# Xonik_Noise_A6_w_logo.net
KiCad netlist of a schematic drawn in EAGLE
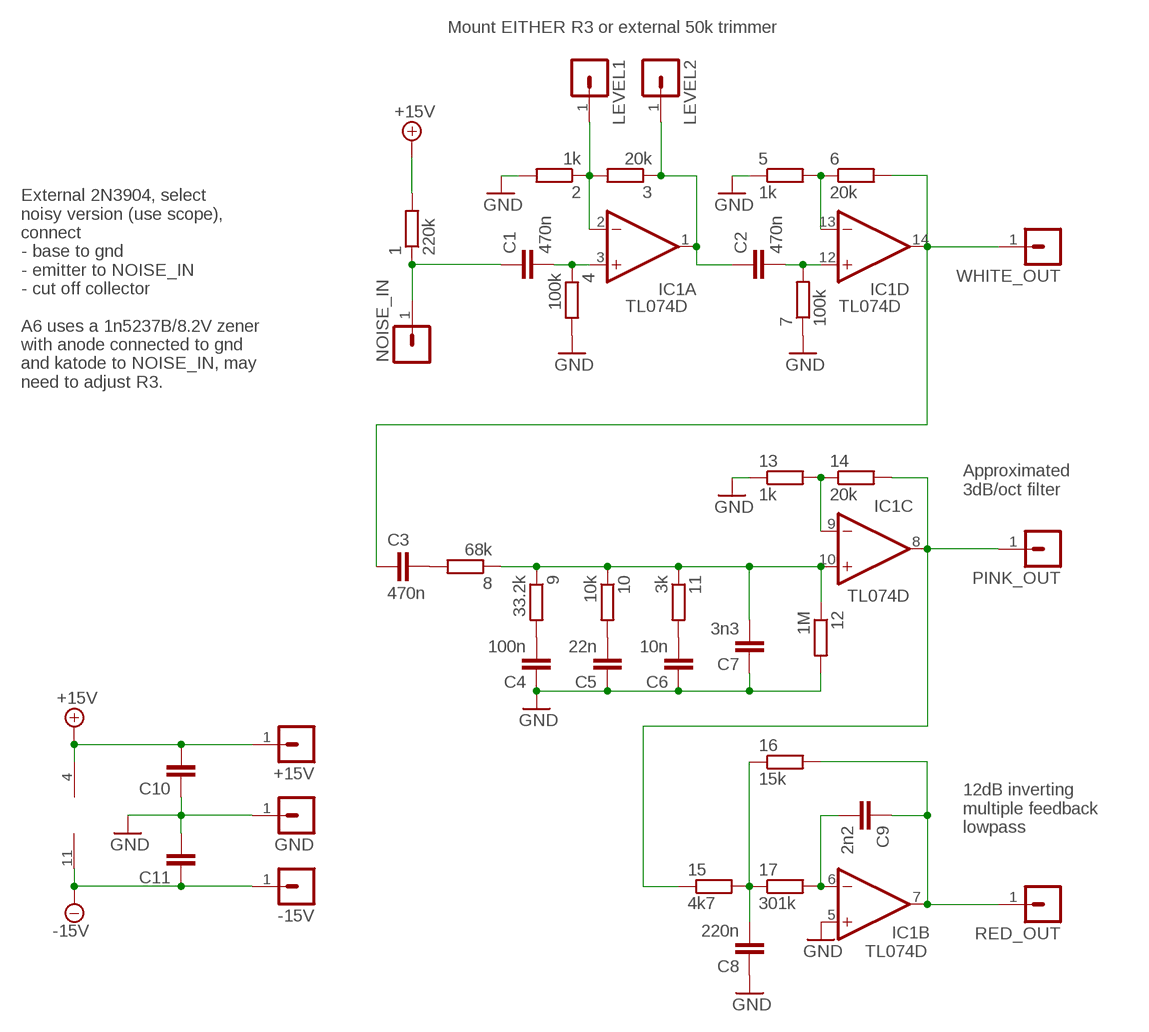
[diagram p0: schematic, sheet 1]

(export (version "E")
  (design (tool "Eeschema 10.0.6"))
  (components
    (comp (ref "+15V")
      (value "MA01-1JP")
      (footprint "eagle-import:SIP-PIN01-1J")
      (libsource (lib "eagle-import") (part "MA01-1JP"))
    )
    (comp (ref "-15V")
      (value "MA01-1JP")
      (footprint "eagle-import:SIP-PIN01-1J")
      (libsource (lib "eagle-import") (part "MA01-1JP"))
    )
    (comp (ref "1")
      (value "220k")
      (footprint "eagle-import:R0805")
      (libsource (lib "eagle-import") (part "R-EU_R0805"))
    )
    (comp (ref "2")
      (value "1k")
      (footprint "eagle-import:R0805")
      (libsource (lib "eagle-import") (part "R-EU_R0805"))
    )
    (comp (ref "3")
      (value "20k")
      (footprint "eagle-import:R0805")
      (libsource (lib "eagle-import") (part "R-EU_R0805"))
    )
    (comp (ref "4")
      (value "100k")
      (footprint "eagle-import:R0805")
      (libsource (lib "eagle-import") (part "R-EU_R0805"))
    )
    (comp (ref "5")
      (value "1k")
      (footprint "eagle-import:R0805")
      (libsource (lib "eagle-import") (part "R-EU_R0805"))
    )
    (comp (ref "6")
      (value "20k")
      (footprint "eagle-import:R0805")
      (libsource (lib "eagle-import") (part "R-EU_R0805"))
    )
    (comp (ref "7")
      (value "100k")
      (footprint "eagle-import:R0805")
      (libsource (lib "eagle-import") (part "R-EU_R0805"))
    )
    (comp (ref "8")
      (value "68k")
      (footprint "eagle-import:R0805")
      (libsource (lib "eagle-import") (part "R-EU_R0805"))
    )
    (comp (ref "9")
      (value "33.2k")
      (footprint "eagle-import:R0805")
      (libsource (lib "eagle-import") (part "R-EU_R0805"))
    )
    (comp (ref "10")
      (value "10k")
      (footprint "eagle-import:R0805")
      (libsource (lib "eagle-import") (part "R-EU_R0805"))
    )
    (comp (ref "11")
      (value "3k")
      (footprint "eagle-import:R0805")
      (libsource (lib "eagle-import") (part "R-EU_R0805"))
    )
    (comp (ref "12")
      (value "1M")
      (footprint "eagle-import:R0805")
      (libsource (lib "eagle-import") (part "R-EU_R0805"))
    )
    (comp (ref "13")
      (value "1k")
      (footprint "eagle-import:R0805")
      (libsource (lib "eagle-import") (part "R-EU_R0805"))
    )
    (comp (ref "14")
      (value "20k")
      (footprint "eagle-import:R0805")
      (libsource (lib "eagle-import") (part "R-EU_R0805"))
    )
    (comp (ref "15")
      (value "4k7")
      (footprint "eagle-import:R0805")
      (libsource (lib "eagle-import") (part "R-EU_R0805"))
    )
    (comp (ref "16")
      (value "15k")
      (footprint "eagle-import:R0805")
      (libsource (lib "eagle-import") (part "R-EU_R0805"))
    )
    (comp (ref "17")
      (value "301k")
      (footprint "eagle-import:R0805")
      (libsource (lib "eagle-import") (part "R-EU_R0805"))
    )
    (comp (ref "C1")
      (value "470n")
      (footprint "eagle-import:C0805")
      (libsource (lib "eagle-import") (part "C-EUC0805"))
    )
    (comp (ref "C2")
      (value "470n")
      (footprint "eagle-import:C0805")
      (libsource (lib "eagle-import") (part "C-EUC0805"))
    )
    (comp (ref "C3")
      (value "470n")
      (footprint "eagle-import:C0805")
      (libsource (lib "eagle-import") (part "C-EUC0805"))
    )
    (comp (ref "C4")
      (value "100n")
      (footprint "eagle-import:C0805")
      (libsource (lib "eagle-import") (part "C-EUC0805"))
    )
    (comp (ref "C5")
      (value "22n")
      (footprint "eagle-import:C0805")
      (libsource (lib "eagle-import") (part "C-EUC0805"))
    )
    (comp (ref "C6")
      (value "10n")
      (footprint "eagle-import:C0805")
      (libsource (lib "eagle-import") (part "C-EUC0805"))
    )
    (comp (ref "C7")
      (value "3n3")
      (footprint "eagle-import:C0805")
      (libsource (lib "eagle-import") (part "C-EUC0805"))
    )
    (comp (ref "C8")
      (value "220n")
      (footprint "eagle-import:C0805")
      (libsource (lib "eagle-import") (part "C-EUC0805"))
    )
    (comp (ref "C9")
      (value "2n2")
      (footprint "eagle-import:C0805")
      (libsource (lib "eagle-import") (part "C-EUC0805"))
    )
    (comp (ref "C10")
      (value "C-EUC0603")
      (footprint "eagle-import:C0603")
      (libsource (lib "eagle-import") (part "C-EUC0603"))
    )
    (comp (ref "C11")
      (value "C-EUC0603")
      (footprint "eagle-import:C0603")
      (libsource (lib "eagle-import") (part "C-EUC0603"))
    )
    (comp (ref "GND")
      (value "MA01-1JP")
      (footprint "eagle-import:SIP-PIN01-1J")
      (libsource (lib "eagle-import") (part "MA01-1JP"))
    )
    (comp (ref "IC1")
      (value "TL074D")
      (footprint "eagle-import:SO14")
      (libsource (lib "eagle-import") (part "TL074D"))
    )
    (comp (ref "LEVEL1")
      (value "MA01-1JP")
      (footprint "eagle-import:SIP-PIN01-1J")
      (libsource (lib "eagle-import") (part "MA01-1JP"))
    )
    (comp (ref "LEVEL2")
      (value "MA01-1JP")
      (footprint "eagle-import:SIP-PIN01-1J")
      (libsource (lib "eagle-import") (part "MA01-1JP"))
    )
    (comp (ref "NOISE_IN")
      (value "MA01-1JP")
      (footprint "eagle-import:SIP-PIN01-1J")
      (libsource (lib "eagle-import") (part "MA01-1JP"))
    )
    (comp (ref "PINK_OUT")
      (value "MA01-1JP")
      (footprint "eagle-import:SIP-PIN01-1J")
      (libsource (lib "eagle-import") (part "MA01-1JP"))
    )
    (comp (ref "RED_OUT")
      (value "MA01-1JP")
      (footprint "eagle-import:SIP-PIN01-1J")
      (libsource (lib "eagle-import") (part "MA01-1JP"))
    )
    (comp (ref "WHITE_OUT")
      (value "MA01-1JP")
      (footprint "eagle-import:SIP-PIN01-1J")
      (libsource (lib "eagle-import") (part "MA01-1JP"))
    )
  )
  (nets
    (net (code "1") (name "+15V") (class "Default")
      (node (ref "+15V") (pin "1") (pinfunction "1_1") (pintype "passive"))
      (node (ref "1") (pin "2") (pinfunction "2_2") (pintype "passive"))
      (node (ref "C10") (pin "2") (pinfunction "2_2") (pintype "passive"))
      (node (ref "IC1") (pin "4") (pinfunction "V+_4") (pintype "power_in"))
    )
    (net (code "2") (name "-15V") (class "Default")
      (node (ref "-15V") (pin "1") (pinfunction "1_1") (pintype "passive"))
      (node (ref "C11") (pin "1") (pinfunction "1_1") (pintype "passive"))
      (node (ref "IC1") (pin "11") (pinfunction "V-_11") (pintype "power_in"))
    )
    (net (code "3") (name "GND") (class "Default")
      (node (ref "12") (pin "2") (pinfunction "2_2") (pintype "passive"))
      (node (ref "13") (pin "1") (pinfunction "1_1") (pintype "passive"))
      (node (ref "2") (pin "2") (pinfunction "2_2") (pintype "passive"))
      (node (ref "4") (pin "2") (pinfunction "2_2") (pintype "passive"))
      (node (ref "5") (pin "1") (pinfunction "1_1") (pintype "passive"))
      (node (ref "7") (pin "1") (pinfunction "1_1") (pintype "passive"))
      (node (ref "C10") (pin "1") (pinfunction "1_1") (pintype "passive"))
      (node (ref "C11") (pin "2") (pinfunction "2_2") (pintype "passive"))
      (node (ref "C4") (pin "1") (pinfunction "1_1") (pintype "passive"))
      (node (ref "C5") (pin "1") (pinfunction "1_1") (pintype "passive"))
      (node (ref "C6") (pin "1") (pinfunction "1_1") (pintype "passive"))
      (node (ref "C7") (pin "1") (pinfunction "1_1") (pintype "passive"))
      (node (ref "C8") (pin "1") (pinfunction "1_1") (pintype "passive"))
      (node (ref "GND") (pin "1") (pinfunction "1_1") (pintype "passive"))
      (node (ref "IC1") (pin "5") (pinfunction "+IN_5") (pintype "input"))
    )
    (net (code "4") (name "Net-(1-Pad1)") (class "Default")
      (node (ref "1") (pin "1") (pinfunction "1_1") (pintype "passive"))
      (node (ref "C1") (pin "1") (pinfunction "1_1") (pintype "passive"))
      (node (ref "NOISE_IN") (pin "1") (pinfunction "1_1") (pintype "passive"))
    )
    (net (code "5") (name "Net-(8-Pad2)") (class "Default")
      (node (ref "8") (pin "2") (pinfunction "2_2") (pintype "passive"))
      (node (ref "C3") (pin "2") (pinfunction "2_2") (pintype "passive"))
    )
    (net (code "6") (name "Net-(9-Pad2)") (class "Default")
      (node (ref "9") (pin "2") (pinfunction "2_2") (pintype "passive"))
      (node (ref "C4") (pin "2") (pinfunction "2_2") (pintype "passive"))
    )
    (net (code "7") (name "Net-(10-Pad2)") (class "Default")
      (node (ref "10") (pin "2") (pinfunction "2_2") (pintype "passive"))
      (node (ref "C5") (pin "2") (pinfunction "2_2") (pintype "passive"))
    )
    (net (code "8") (name "Net-(11-Pad2)") (class "Default")
      (node (ref "11") (pin "2") (pinfunction "2_2") (pintype "passive"))
      (node (ref "C6") (pin "2") (pinfunction "2_2") (pintype "passive"))
    )
    (net (code "9") (name "Net-(15-Pad2)") (class "Default")
      (node (ref "15") (pin "2") (pinfunction "2_2") (pintype "passive"))
      (node (ref "16") (pin "1") (pinfunction "1_1") (pintype "passive"))
      (node (ref "17") (pin "1") (pinfunction "1_1") (pintype "passive"))
      (node (ref "C8") (pin "2") (pinfunction "2_2") (pintype "passive"))
    )
    (net (code "10") (name "Net-(IC1A-+IN)") (class "Default")
      (node (ref "4") (pin "1") (pinfunction "1_1") (pintype "passive"))
      (node (ref "C1") (pin "2") (pinfunction "2_2") (pintype "passive"))
      (node (ref "IC1") (pin "3") (pinfunction "+IN_3") (pintype "input"))
    )
    (net (code "11") (name "Net-(IC1A--IN)") (class "Default")
      (node (ref "2") (pin "1") (pinfunction "1_1") (pintype "passive"))
      (node (ref "3") (pin "2") (pinfunction "2_2") (pintype "passive"))
      (node (ref "IC1") (pin "2") (pinfunction "-IN_2") (pintype "input"))
      (node (ref "LEVEL1") (pin "1") (pinfunction "1_1") (pintype "passive"))
    )
    (net (code "12") (name "Net-(IC1A-OUT)") (class "Default")
      (node (ref "3") (pin "1") (pinfunction "1_1") (pintype "passive"))
      (node (ref "C2") (pin "1") (pinfunction "1_1") (pintype "passive"))
      (node (ref "IC1") (pin "1") (pinfunction "OUT_1") (pintype "output"))
      (node (ref "LEVEL2") (pin "1") (pinfunction "1_1") (pintype "passive"))
    )
    (net (code "13") (name "Net-(IC1B--IN)") (class "Default")
      (node (ref "17") (pin "2") (pinfunction "2_2") (pintype "passive"))
      (node (ref "C9") (pin "2") (pinfunction "2_2") (pintype "passive"))
      (node (ref "IC1") (pin "6") (pinfunction "-IN_6") (pintype "input"))
    )
    (net (code "14") (name "Net-(IC1B-OUT)") (class "Default")
      (node (ref "16") (pin "2") (pinfunction "2_2") (pintype "passive"))
      (node (ref "C9") (pin "1") (pinfunction "1_1") (pintype "passive"))
      (node (ref "IC1") (pin "7") (pinfunction "OUT_7") (pintype "output"))
      (node (ref "RED_OUT") (pin "1") (pinfunction "1_1") (pintype "passive"))
    )
    (net (code "15") (name "Net-(IC1C-+IN)") (class "Default")
      (node (ref "10") (pin "1") (pinfunction "1_1") (pintype "passive"))
      (node (ref "11") (pin "1") (pinfunction "1_1") (pintype "passive"))
      (node (ref "12") (pin "1") (pinfunction "1_1") (pintype "passive"))
      (node (ref "8") (pin "1") (pinfunction "1_1") (pintype "passive"))
      (node (ref "9") (pin "1") (pinfunction "1_1") (pintype "passive"))
      (node (ref "C7") (pin "2") (pinfunction "2_2") (pintype "passive"))
      (node (ref "IC1") (pin "10") (pinfunction "+IN_10") (pintype "input"))
    )
    (net (code "16") (name "Net-(IC1C--IN)") (class "Default")
      (node (ref "13") (pin "2") (pinfunction "2_2") (pintype "passive"))
      (node (ref "14") (pin "1") (pinfunction "1_1") (pintype "passive"))
      (node (ref "IC1") (pin "9") (pinfunction "-IN_9") (pintype "input"))
    )
    (net (code "17") (name "Net-(IC1C-OUT)") (class "Default")
      (node (ref "14") (pin "2") (pinfunction "2_2") (pintype "passive"))
      (node (ref "15") (pin "1") (pinfunction "1_1") (pintype "passive"))
      (node (ref "IC1") (pin "8") (pinfunction "OUT_8") (pintype "output"))
      (node (ref "PINK_OUT") (pin "1") (pinfunction "1_1") (pintype "passive"))
    )
    (net (code "18") (name "Net-(IC1D-+IN)") (class "Default")
      (node (ref "7") (pin "2") (pinfunction "2_2") (pintype "passive"))
      (node (ref "C2") (pin "2") (pinfunction "2_2") (pintype "passive"))
      (node (ref "IC1") (pin "12") (pinfunction "+IN_12") (pintype "input"))
    )
    (net (code "19") (name "Net-(IC1D--IN)") (class "Default")
      (node (ref "5") (pin "2") (pinfunction "2_2") (pintype "passive"))
      (node (ref "6") (pin "1") (pinfunction "1_1") (pintype "passive"))
      (node (ref "IC1") (pin "13") (pinfunction "-IN_13") (pintype "input"))
    )
    (net (code "20") (name "Net-(IC1D-OUT)") (class "Default")
      (node (ref "6") (pin "2") (pinfunction "2_2") (pintype "passive"))
      (node (ref "C3") (pin "1") (pinfunction "1_1") (pintype "passive"))
      (node (ref "IC1") (pin "14") (pinfunction "OUT_14") (pintype "output"))
      (node (ref "WHITE_OUT") (pin "1") (pinfunction "1_1") (pintype "passive"))
    )
  )
)
